# ADDA.net
KiCad netlist of a schematic drawn in EasyEDA Pro
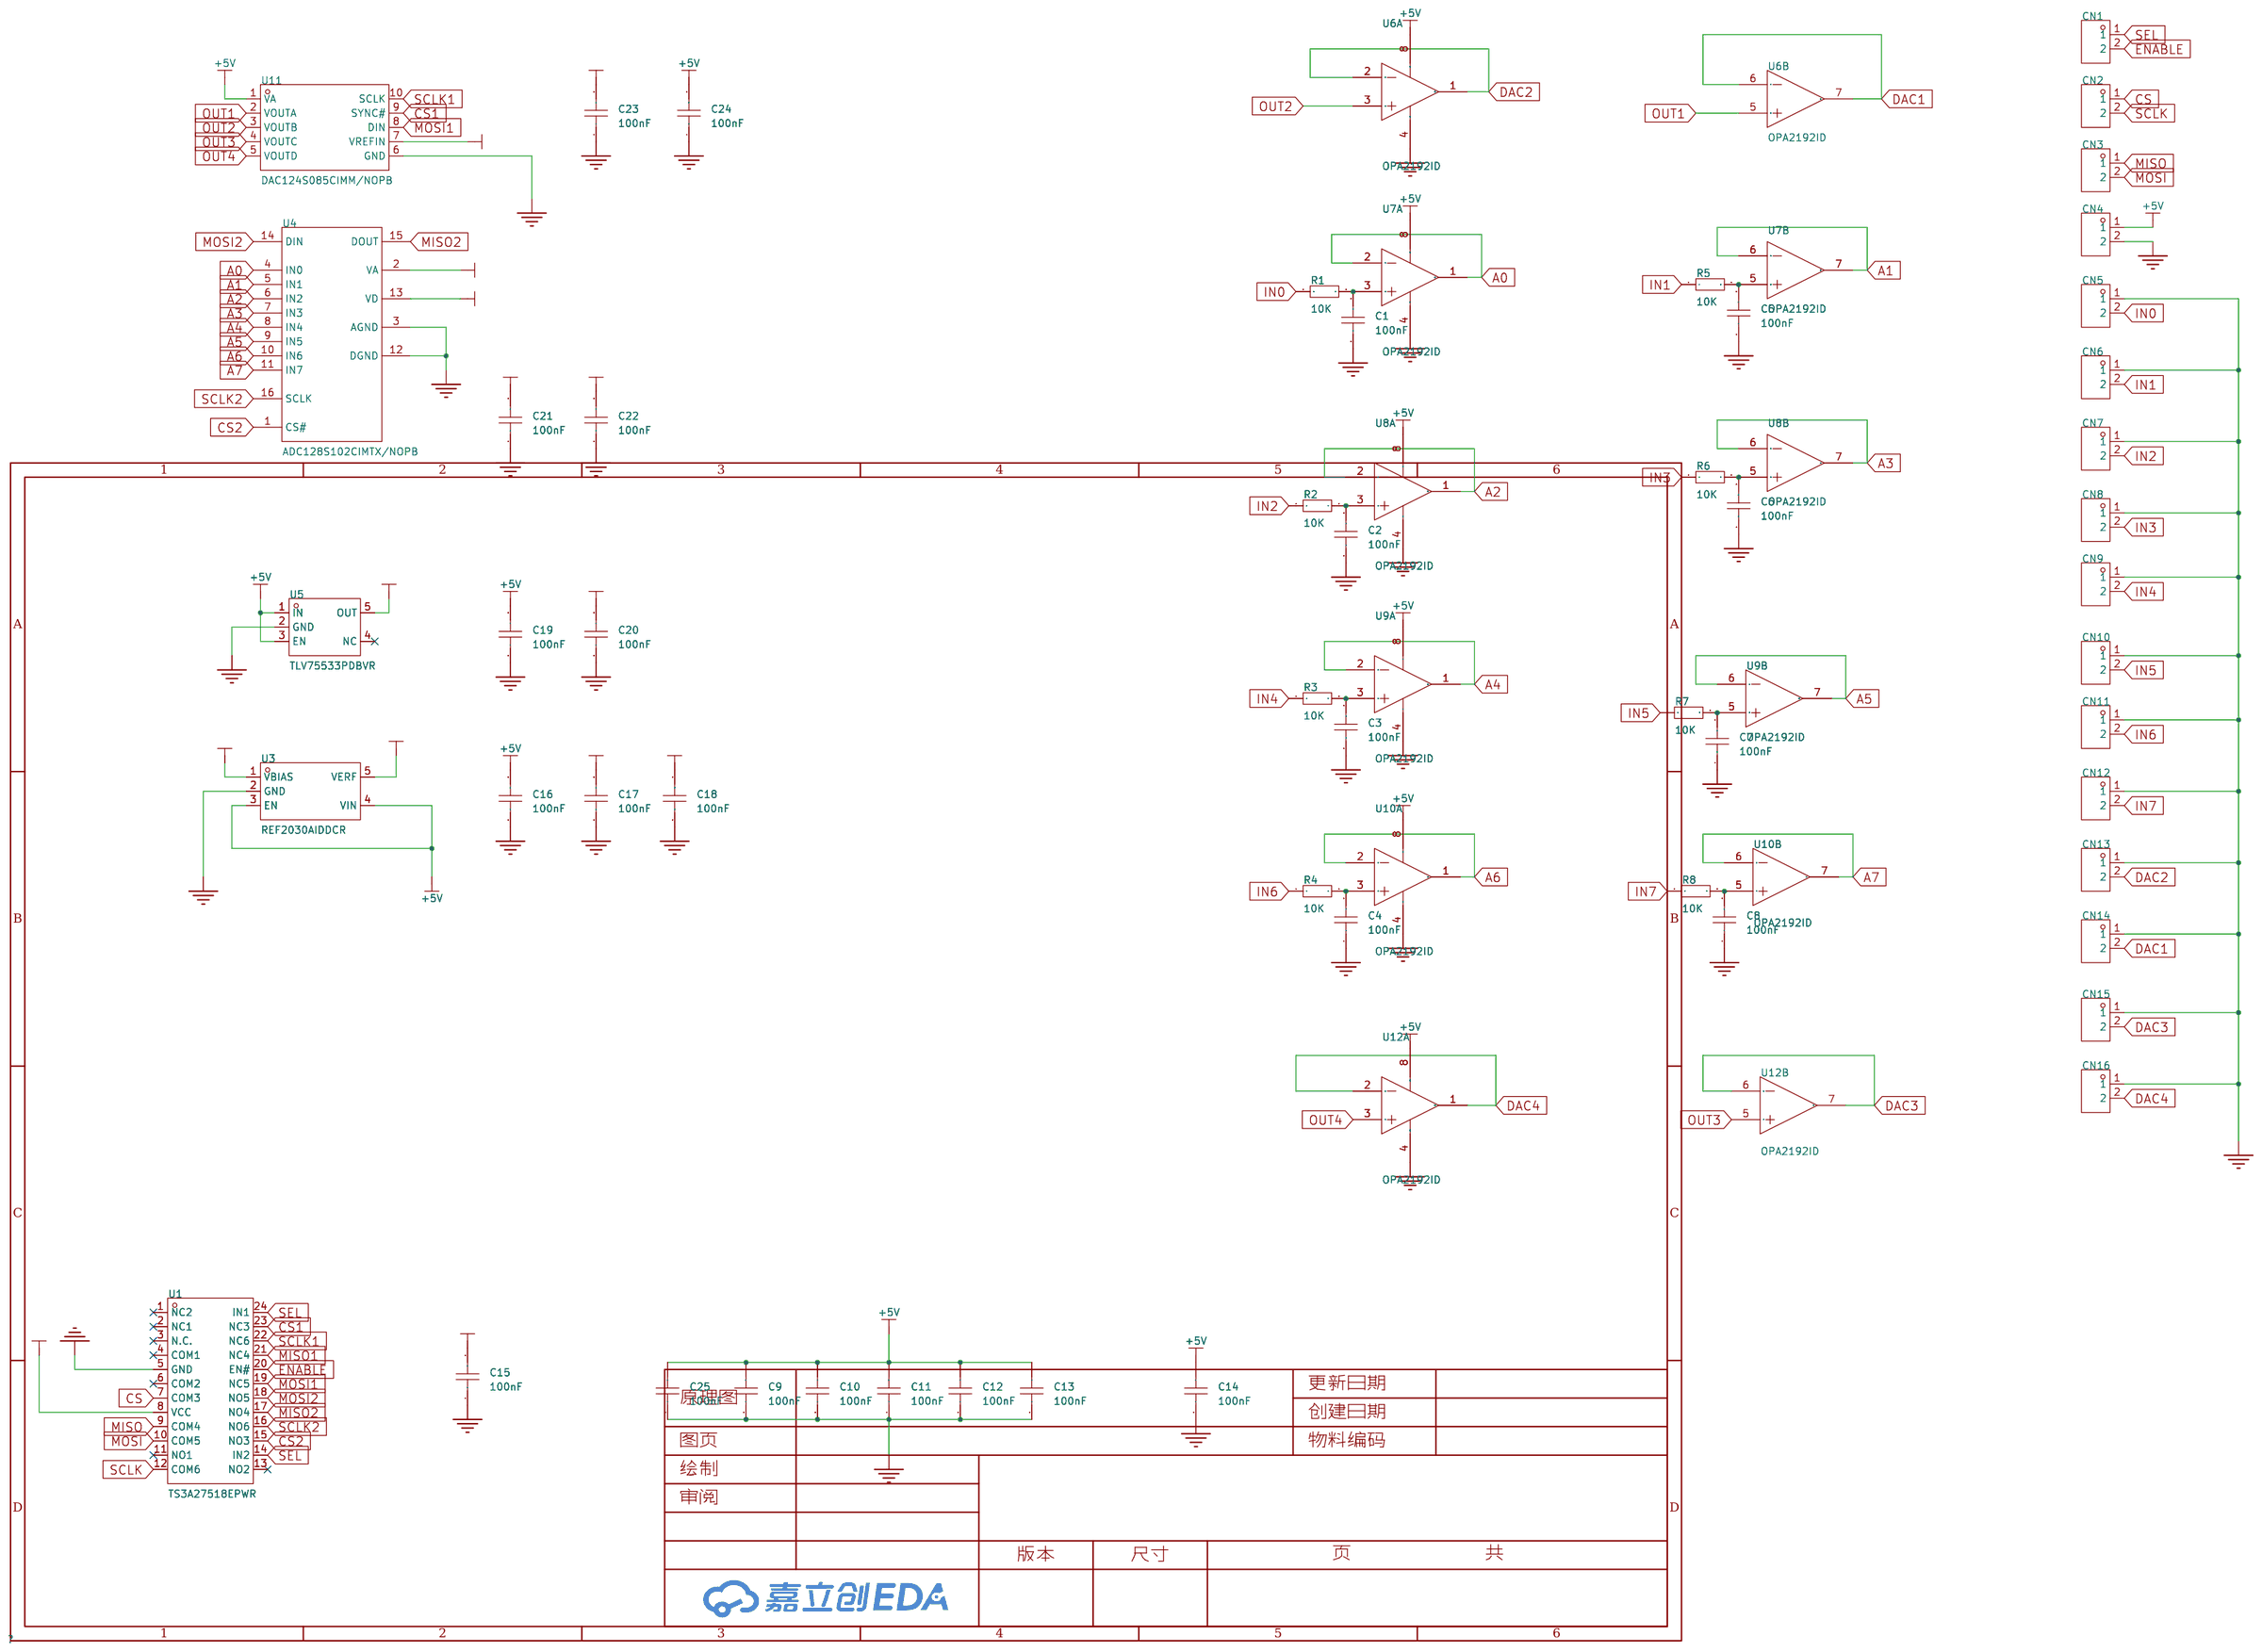
[diagram p0: schematic sheet]

(export (version "E")
  (design (tool "Eeschema 10.0.6"))
  (components
    (comp (ref "C1")
      (value "100nF")
      (footprint "easyedapro:C0805")
      (libsource (lib "easyedapro") (part "CapAcitance"))
    )
    (comp (ref "C2")
      (value "100nF")
      (footprint "easyedapro:C0805")
      (libsource (lib "easyedapro") (part "CapAcitance"))
    )
    (comp (ref "C3")
      (value "100nF")
      (footprint "easyedapro:C0805")
      (libsource (lib "easyedapro") (part "CapAcitance"))
    )
    (comp (ref "C4")
      (value "100nF")
      (footprint "easyedapro:C0805")
      (libsource (lib "easyedapro") (part "CapAcitance"))
    )
    (comp (ref "C5")
      (value "100nF")
      (footprint "easyedapro:C0805")
      (libsource (lib "easyedapro") (part "CapAcitance"))
    )
    (comp (ref "C6")
      (value "100nF")
      (footprint "easyedapro:C0805")
      (libsource (lib "easyedapro") (part "CapAcitance"))
    )
    (comp (ref "C7")
      (value "100nF")
      (footprint "easyedapro:C0805")
      (libsource (lib "easyedapro") (part "CapAcitance"))
    )
    (comp (ref "C8")
      (value "100nF")
      (footprint "easyedapro:C0805")
      (libsource (lib "easyedapro") (part "CapAcitance"))
    )
    (comp (ref "C9")
      (value "100nF")
      (footprint "easyedapro:C0805")
      (libsource (lib "easyedapro") (part "CapAcitance"))
    )
    (comp (ref "C10")
      (value "100nF")
      (footprint "easyedapro:C0805")
      (libsource (lib "easyedapro") (part "CapAcitance"))
    )
    (comp (ref "C11")
      (value "100nF")
      (footprint "easyedapro:C0805")
      (libsource (lib "easyedapro") (part "CapAcitance"))
    )
    (comp (ref "C12")
      (value "100nF")
      (footprint "easyedapro:C0805")
      (libsource (lib "easyedapro") (part "CapAcitance"))
    )
    (comp (ref "C13")
      (value "100nF")
      (footprint "easyedapro:C0805")
      (libsource (lib "easyedapro") (part "CapAcitance"))
    )
    (comp (ref "C14")
      (value "100nF")
      (footprint "easyedapro:C0805")
      (libsource (lib "easyedapro") (part "CapAcitance"))
    )
    (comp (ref "C15")
      (value "100nF")
      (footprint "easyedapro:C0805")
      (libsource (lib "easyedapro") (part "CapAcitance"))
    )
    (comp (ref "C16")
      (value "100nF")
      (footprint "easyedapro:C0805")
      (libsource (lib "easyedapro") (part "CapAcitance"))
    )
    (comp (ref "C17")
      (value "100nF")
      (footprint "easyedapro:C0805")
      (libsource (lib "easyedapro") (part "CapAcitance"))
    )
    (comp (ref "C18")
      (value "100nF")
      (footprint "easyedapro:C0805")
      (libsource (lib "easyedapro") (part "CapAcitance"))
    )
    (comp (ref "C19")
      (value "100nF")
      (footprint "easyedapro:C0805")
      (libsource (lib "easyedapro") (part "CapAcitance"))
    )
    (comp (ref "C20")
      (value "100nF")
      (footprint "easyedapro:C0805")
      (libsource (lib "easyedapro") (part "CapAcitance"))
    )
    (comp (ref "C21")
      (value "100nF")
      (footprint "easyedapro:C0805")
      (libsource (lib "easyedapro") (part "CapAcitance"))
    )
    (comp (ref "C22")
      (value "100nF")
      (footprint "easyedapro:C0805")
      (libsource (lib "easyedapro") (part "CapAcitance"))
    )
    (comp (ref "C23")
      (value "100nF")
      (footprint "easyedapro:C0805")
      (libsource (lib "easyedapro") (part "CapAcitance"))
    )
    (comp (ref "C24")
      (value "100nF")
      (footprint "easyedapro:C0805")
      (libsource (lib "easyedapro") (part "CapAcitance"))
    )
    (comp (ref "C25")
      (value "100nF")
      (footprint "easyedapro:C0805")
      (libsource (lib "easyedapro") (part "CapAcitance"))
    )
    (comp (ref "CN1")
      (value "CON2-2.54*2P")
      (footprint "easyedapro:CONN-TH_2P-P2.54-V")
      (libsource (lib "easyedapro") (part "CON2-2.54*2P"))
    )
    (comp (ref "CN2")
      (value "CON2-2.54*2P")
      (footprint "easyedapro:CONN-TH_2P-P2.54-V")
      (libsource (lib "easyedapro") (part "CON2-2.54*2P"))
    )
    (comp (ref "CN3")
      (value "CON2-2.54*2P")
      (footprint "easyedapro:CONN-TH_2P-P2.54-V")
      (libsource (lib "easyedapro") (part "CON2-2.54*2P"))
    )
    (comp (ref "CN4")
      (value "CON2-2.54*2P")
      (footprint "easyedapro:CONN-TH_2P-P2.54-V")
      (libsource (lib "easyedapro") (part "CON2-2.54*2P"))
    )
    (comp (ref "CN5")
      (value "CON2-2.54*2P")
      (footprint "easyedapro:CONN-TH_2P-P2.54-V")
      (libsource (lib "easyedapro") (part "CON2-2.54*2P"))
    )
    (comp (ref "CN6")
      (value "CON2-2.54*2P")
      (footprint "easyedapro:CONN-TH_2P-P2.54-V")
      (libsource (lib "easyedapro") (part "CON2-2.54*2P"))
    )
    (comp (ref "CN7")
      (value "CON2-2.54*2P")
      (footprint "easyedapro:CONN-TH_2P-P2.54-V")
      (libsource (lib "easyedapro") (part "CON2-2.54*2P"))
    )
    (comp (ref "CN8")
      (value "CON2-2.54*2P")
      (footprint "easyedapro:CONN-TH_2P-P2.54-V")
      (libsource (lib "easyedapro") (part "CON2-2.54*2P"))
    )
    (comp (ref "CN9")
      (value "CON2-2.54*2P")
      (footprint "easyedapro:CONN-TH_2P-P2.54-V")
      (libsource (lib "easyedapro") (part "CON2-2.54*2P"))
    )
    (comp (ref "CN10")
      (value "CON2-2.54*2P")
      (footprint "easyedapro:CONN-TH_2P-P2.54-V")
      (libsource (lib "easyedapro") (part "CON2-2.54*2P"))
    )
    (comp (ref "CN11")
      (value "CON2-2.54*2P")
      (footprint "easyedapro:CONN-TH_2P-P2.54-V")
      (libsource (lib "easyedapro") (part "CON2-2.54*2P"))
    )
    (comp (ref "CN12")
      (value "CON2-2.54*2P")
      (footprint "easyedapro:CONN-TH_2P-P2.54-V")
      (libsource (lib "easyedapro") (part "CON2-2.54*2P"))
    )
    (comp (ref "CN13")
      (value "CON2-2.54*2P")
      (footprint "easyedapro:CONN-TH_2P-P2.54-V")
      (libsource (lib "easyedapro") (part "CON2-2.54*2P"))
    )
    (comp (ref "CN14")
      (value "CON2-2.54*2P")
      (footprint "easyedapro:CONN-TH_2P-P2.54-V")
      (libsource (lib "easyedapro") (part "CON2-2.54*2P"))
    )
    (comp (ref "CN15")
      (value "CON2-2.54*2P")
      (footprint "easyedapro:CONN-TH_2P-P2.54-V")
      (libsource (lib "easyedapro") (part "CON2-2.54*2P"))
    )
    (comp (ref "CN16")
      (value "CON2-2.54*2P")
      (footprint "easyedapro:CONN-TH_2P-P2.54-V")
      (libsource (lib "easyedapro") (part "CON2-2.54*2P"))
    )
    (comp (ref "R1") (value "10K") (footprint "easyedapro:R0805") (libsource (lib "easyedapro") (part "电阻")))
    (comp (ref "R2") (value "10K") (footprint "easyedapro:R0805") (libsource (lib "easyedapro") (part "电阻")))
    (comp (ref "R3") (value "10K") (footprint "easyedapro:R0805") (libsource (lib "easyedapro") (part "电阻")))
    (comp (ref "R4") (value "10K") (footprint "easyedapro:R0805") (libsource (lib "easyedapro") (part "电阻")))
    (comp (ref "R5") (value "10K") (footprint "easyedapro:R0805") (libsource (lib "easyedapro") (part "电阻")))
    (comp (ref "R6") (value "10K") (footprint "easyedapro:R0805") (libsource (lib "easyedapro") (part "电阻")))
    (comp (ref "R7") (value "10K") (footprint "easyedapro:R0805") (libsource (lib "easyedapro") (part "电阻")))
    (comp (ref "R8") (value "10K") (footprint "easyedapro:R0805") (libsource (lib "easyedapro") (part "电阻")))
    (comp (ref "U1")
      (value "TS3A27518EPWR")
      (footprint "easyedapro:TSSOP-24_L7.8-W4.4-P0.65-LS6.4-BL")
      (description "开关电路:-;通道数:6;导通电阻:6.2Ω;")
      (fields (field (name "Manufacturer") "TI(德州仪器)"))
      (libsource (lib "easyedapro") (part "TS3A27518EPWR"))
    )
    (comp (ref "U3")
      (value "REF2030AIDDCR")
      (footprint "easyedapro:SOT-23-5_L2.9-W1.6-P0.95-LS2.8-BL")
      (description "输出类型:固定;输入电压:3.02V~5.5V;输出电压:1.5V；3V;输出电流:20mA;精度:±0.05%;")
      (fields (field (name "Manufacturer") "TI(德州仪器)"))
      (libsource (lib "easyedapro") (part "REF2030AIDDCR"))
    )
    (comp (ref "U4")
      (value "ADC128S102CIMTX/NOPB")
      (footprint "easyedapro:TSSOP-16_L5.0-W4.4-P0.65-LS6.4-BL")
      (description "接口:SPI；DSP;电源电压:2.7V~5.25V;采样率:1MHz;分辨率:12位;")
      (fields (field (name "Manufacturer") "TI(德州仪器)"))
      (libsource (lib "easyedapro") (part "ADC128S102CIMTX/NOPB"))
    )
    (comp (ref "U5")
      (value "TLV75533PDBVR")
      (footprint "easyedapro:SOT-23-5_L3.0-W1.7-P0.95-LS2.8-BR")
      (description "输出类型:固定;最大输入电压:5.5V;输出电压:3.3V;输出电流:500mA;电源纹波抑制比(PSRR):52dB;输出极性:正极;")
      (fields (field (name "Manufacturer") "TI(德州仪器)"))
      (libsource (lib "easyedapro") (part "TLV75533PDBVR"))
    )
    (comp (ref "U6")
      (value "OPA2192ID")
      (footprint "easyedapro:SOIC-8_L4.9-W3.9-P1.27-LS6.0-BL")
      (description "放大器数:双路;增益带宽积(GBP):10MHz;输入偏置电流(Ib):5pA;输入失调电压(Vos):5uV;压摆率(SR):20V/us;带宽(-3db):-;轨到轨:-;")
      (fields (field (name "Manufacturer") "TI(德州仪器)"))
      (libsource (lib "easyedapro") (part "OPA2192ID"))
    )
    (comp (ref "U7")
      (value "OPA2192ID")
      (footprint "easyedapro:SOIC-8_L4.9-W3.9-P1.27-LS6.0-BL")
      (description "放大器数:双路;增益带宽积(GBP):10MHz;输入偏置电流(Ib):5pA;输入失调电压(Vos):5uV;压摆率(SR):20V/us;带宽(-3db):-;轨到轨:-;")
      (fields (field (name "Manufacturer") "TI(德州仪器)"))
      (libsource (lib "easyedapro") (part "OPA2192ID"))
    )
    (comp (ref "U8")
      (value "OPA2192ID")
      (footprint "easyedapro:SOIC-8_L4.9-W3.9-P1.27-LS6.0-BL")
      (description "放大器数:双路;增益带宽积(GBP):10MHz;输入偏置电流(Ib):5pA;输入失调电压(Vos):5uV;压摆率(SR):20V/us;带宽(-3db):-;轨到轨:-;")
      (fields (field (name "Manufacturer") "TI(德州仪器)"))
      (libsource (lib "easyedapro") (part "OPA2192ID"))
    )
    (comp (ref "U9")
      (value "OPA2192ID")
      (footprint "easyedapro:SOIC-8_L4.9-W3.9-P1.27-LS6.0-BL")
      (description "放大器数:双路;增益带宽积(GBP):10MHz;输入偏置电流(Ib):5pA;输入失调电压(Vos):5uV;压摆率(SR):20V/us;带宽(-3db):-;轨到轨:-;")
      (fields (field (name "Manufacturer") "TI(德州仪器)"))
      (libsource (lib "easyedapro") (part "OPA2192ID"))
    )
    (comp (ref "U10")
      (value "OPA2192ID")
      (footprint "easyedapro:SOIC-8_L4.9-W3.9-P1.27-LS6.0-BL")
      (description "放大器数:双路;增益带宽积(GBP):10MHz;输入偏置电流(Ib):5pA;输入失调电压(Vos):5uV;压摆率(SR):20V/us;带宽(-3db):-;轨到轨:-;")
      (fields (field (name "Manufacturer") "TI(德州仪器)"))
      (libsource (lib "easyedapro") (part "OPA2192ID"))
    )
    (comp (ref "U11")
      (value "DAC124S085CIMM/NOPB")
      (footprint "easyedapro:VSSOP-10_L3.0-W3.0-P0.50-LS4.9-BL")
      (description "分辨率:12位;接口类型:SPI；QSPI；MICROWIRE;工作电压:2.7V~5.5V;稳定时间:8.5us;INL/DNL:8LSB;")
      (fields (field (name "Manufacturer") "TI(德州仪器)"))
      (libsource (lib "easyedapro") (part "DAC124S085CIMM/NOPB"))
    )
    (comp (ref "U12")
      (value "OPA2192ID")
      (footprint "easyedapro:SOIC-8_L4.9-W3.9-P1.27-LS6.0-BL")
      (description "放大器数:双路;增益带宽积(GBP):10MHz;输入偏置电流(Ib):5pA;输入失调电压(Vos):5uV;压摆率(SR):20V/us;带宽(-3db):-;轨到轨:-;")
      (fields (field (name "Manufacturer") "TI(德州仪器)"))
      (libsource (lib "easyedapro") (part "OPA2192ID"))
    )
  )
  (nets
    (net (code "1") (name "+5V") (class "Default")
      (node (ref "C10") (pin "2") (pinfunction "2_2") (pintype "input"))
      (node (ref "C11") (pin "2") (pinfunction "2_2") (pintype "input"))
      (node (ref "C12") (pin "2") (pinfunction "2_2") (pintype "input"))
      (node (ref "C13") (pin "2") (pinfunction "2_2") (pintype "input"))
      (node (ref "C14") (pin "2") (pinfunction "2_2") (pintype "input"))
      (node (ref "C16") (pin "2") (pinfunction "2_2") (pintype "input"))
      (node (ref "C19") (pin "2") (pinfunction "2_2") (pintype "input"))
      (node (ref "C24") (pin "2") (pinfunction "2_2") (pintype "input"))
      (node (ref "C25") (pin "2") (pinfunction "2_2") (pintype "input"))
      (node (ref "C9") (pin "2") (pinfunction "2_2") (pintype "input"))
      (node (ref "CN4") (pin "1") (pinfunction "1_1") (pintype "unspecified"))
      (node (ref "U10") (pin "8") (pinfunction "VCC_8") (pintype "unspecified"))
      (node (ref "U11") (pin "1") (pinfunction "VA_1") (pintype "unspecified"))
      (node (ref "U12") (pin "8") (pinfunction "VCC_8") (pintype "unspecified"))
      (node (ref "U3") (pin "3") (pinfunction "EN_3") (pintype "unspecified"))
      (node (ref "U3") (pin "4") (pinfunction "VIN_4") (pintype "unspecified"))
      (node (ref "U5") (pin "1") (pinfunction "IN_1") (pintype "unspecified"))
      (node (ref "U5") (pin "3") (pinfunction "EN_3") (pintype "unspecified"))
      (node (ref "U6") (pin "8") (pinfunction "VCC_8") (pintype "unspecified"))
      (node (ref "U7") (pin "8") (pinfunction "VCC_8") (pintype "unspecified"))
      (node (ref "U8") (pin "8") (pinfunction "VCC_8") (pintype "unspecified"))
      (node (ref "U9") (pin "8") (pinfunction "VCC_8") (pintype "unspecified"))
    )
    (net (code "2") (name "1.5V") (class "Default")
      (node (ref "C17") (pin "2") (pinfunction "2_2") (pintype "input"))
      (node (ref "U3") (pin "1") (pinfunction "VBIAS_1") (pintype "unspecified"))
    )
    (net (code "3") (name "3.3V") (class "Default")
      (node (ref "C15") (pin "2") (pinfunction "2_2") (pintype "input"))
      (node (ref "C20") (pin "2") (pinfunction "2_2") (pintype "input"))
      (node (ref "C21") (pin "2") (pinfunction "2_2") (pintype "input"))
      (node (ref "U1") (pin "8") (pinfunction "VCC_8") (pintype "unspecified"))
      (node (ref "U4") (pin "13") (pinfunction "VD_13") (pintype "unspecified"))
      (node (ref "U5") (pin "5") (pinfunction "OUT_5") (pintype "unspecified"))
    )
    (net (code "4") (name "3V") (class "Default")
      (node (ref "C18") (pin "2") (pinfunction "2_2") (pintype "input"))
      (node (ref "C22") (pin "2") (pinfunction "2_2") (pintype "input"))
      (node (ref "C23") (pin "2") (pinfunction "2_2") (pintype "input"))
      (node (ref "U11") (pin "7") (pinfunction "VREFIN_7") (pintype "unspecified"))
      (node (ref "U3") (pin "5") (pinfunction "VERF_5") (pintype "unspecified"))
      (node (ref "U4") (pin "2") (pinfunction "VA_2") (pintype "unspecified"))
    )
    (net (code "5") (name "A0") (class "Default")
      (node (ref "U4") (pin "4") (pinfunction "IN0_4") (pintype "unspecified"))
      (node (ref "U7") (pin "1") (pinfunction "OUT1_1") (pintype "output"))
      (node (ref "U7") (pin "2") (pinfunction "IN1-_2") (pintype "unspecified"))
    )
    (net (code "6") (name "A1") (class "Default")
      (node (ref "U4") (pin "5") (pinfunction "IN1_5") (pintype "unspecified"))
      (node (ref "U7") (pin "6") (pinfunction "IN2-_6") (pintype "unspecified"))
      (node (ref "U7") (pin "7") (pinfunction "OUT2_7") (pintype "output"))
    )
    (net (code "7") (name "A2") (class "Default")
      (node (ref "U4") (pin "6") (pinfunction "IN2_6") (pintype "unspecified"))
      (node (ref "U8") (pin "1") (pinfunction "OUT1_1") (pintype "output"))
      (node (ref "U8") (pin "2") (pinfunction "IN1-_2") (pintype "unspecified"))
    )
    (net (code "8") (name "A3") (class "Default")
      (node (ref "U4") (pin "7") (pinfunction "IN3_7") (pintype "unspecified"))
      (node (ref "U8") (pin "6") (pinfunction "IN2-_6") (pintype "unspecified"))
      (node (ref "U8") (pin "7") (pinfunction "OUT2_7") (pintype "output"))
    )
    (net (code "9") (name "A4") (class "Default")
      (node (ref "U4") (pin "8") (pinfunction "IN4_8") (pintype "unspecified"))
      (node (ref "U9") (pin "1") (pinfunction "OUT1_1") (pintype "output"))
      (node (ref "U9") (pin "2") (pinfunction "IN1-_2") (pintype "unspecified"))
    )
    (net (code "10") (name "A5") (class "Default")
      (node (ref "U4") (pin "9") (pinfunction "IN5_9") (pintype "unspecified"))
      (node (ref "U9") (pin "6") (pinfunction "IN2-_6") (pintype "unspecified"))
      (node (ref "U9") (pin "7") (pinfunction "OUT2_7") (pintype "output"))
    )
    (net (code "11") (name "A6") (class "Default")
      (node (ref "U10") (pin "1") (pinfunction "OUT1_1") (pintype "output"))
      (node (ref "U10") (pin "2") (pinfunction "IN1-_2") (pintype "unspecified"))
      (node (ref "U4") (pin "10") (pinfunction "IN6_10") (pintype "unspecified"))
    )
    (net (code "12") (name "A7") (class "Default")
      (node (ref "U10") (pin "6") (pinfunction "IN2-_6") (pintype "unspecified"))
      (node (ref "U10") (pin "7") (pinfunction "OUT2_7") (pintype "output"))
      (node (ref "U4") (pin "11") (pinfunction "IN7_11") (pintype "unspecified"))
    )
    (net (code "13") (name "CS") (class "Default")
      (node (ref "CN2") (pin "1") (pinfunction "1_1") (pintype "unspecified"))
      (node (ref "U1") (pin "7") (pinfunction "COM3_7") (pintype "unspecified"))
    )
    (net (code "14") (name "CS1") (class "Default")
      (node (ref "U1") (pin "23") (pinfunction "NC3_23") (pintype "unspecified"))
      (node (ref "U11") (pin "9") (pinfunction "SYNC#_9") (pintype "unspecified"))
    )
    (net (code "15") (name "CS2") (class "Default")
      (node (ref "U1") (pin "15") (pinfunction "NO3_15") (pintype "unspecified"))
      (node (ref "U4") (pin "1") (pinfunction "CS#_1") (pintype "unspecified"))
    )
    (net (code "16") (name "DAC1") (class "Default")
      (node (ref "CN14") (pin "2") (pinfunction "2_2") (pintype "unspecified"))
      (node (ref "U6") (pin "6") (pinfunction "IN2-_6") (pintype "unspecified"))
      (node (ref "U6") (pin "7") (pinfunction "OUT2_7") (pintype "output"))
    )
    (net (code "17") (name "DAC2") (class "Default")
      (node (ref "CN13") (pin "2") (pinfunction "2_2") (pintype "unspecified"))
      (node (ref "U6") (pin "1") (pinfunction "OUT1_1") (pintype "output"))
      (node (ref "U6") (pin "2") (pinfunction "IN1-_2") (pintype "unspecified"))
    )
    (net (code "18") (name "DAC3") (class "Default")
      (node (ref "CN15") (pin "2") (pinfunction "2_2") (pintype "unspecified"))
      (node (ref "U12") (pin "6") (pinfunction "IN2-_6") (pintype "unspecified"))
      (node (ref "U12") (pin "7") (pinfunction "OUT2_7") (pintype "output"))
    )
    (net (code "19") (name "DAC4") (class "Default")
      (node (ref "CN16") (pin "2") (pinfunction "2_2") (pintype "unspecified"))
      (node (ref "U12") (pin "1") (pinfunction "OUT1_1") (pintype "output"))
      (node (ref "U12") (pin "2") (pinfunction "IN1-_2") (pintype "unspecified"))
    )
    (net (code "20") (name "ENABLE") (class "Default")
      (node (ref "CN1") (pin "2") (pinfunction "2_2") (pintype "unspecified"))
      (node (ref "U1") (pin "20") (pinfunction "EN#_20") (pintype "unspecified"))
    )
    (net (code "21") (name "GND") (class "Default")
      (node (ref "C1") (pin "1") (pinfunction "1_1") (pintype "input"))
      (node (ref "C10") (pin "1") (pinfunction "1_1") (pintype "input"))
      (node (ref "C11") (pin "1") (pinfunction "1_1") (pintype "input"))
      (node (ref "C12") (pin "1") (pinfunction "1_1") (pintype "input"))
      (node (ref "C13") (pin "1") (pinfunction "1_1") (pintype "input"))
      (node (ref "C14") (pin "1") (pinfunction "1_1") (pintype "input"))
      (node (ref "C15") (pin "1") (pinfunction "1_1") (pintype "input"))
      (node (ref "C16") (pin "1") (pinfunction "1_1") (pintype "input"))
      (node (ref "C17") (pin "1") (pinfunction "1_1") (pintype "input"))
      (node (ref "C18") (pin "1") (pinfunction "1_1") (pintype "input"))
      (node (ref "C19") (pin "1") (pinfunction "1_1") (pintype "input"))
      (node (ref "C2") (pin "1") (pinfunction "1_1") (pintype "input"))
      (node (ref "C20") (pin "1") (pinfunction "1_1") (pintype "input"))
      (node (ref "C21") (pin "1") (pinfunction "1_1") (pintype "input"))
      (node (ref "C22") (pin "1") (pinfunction "1_1") (pintype "input"))
      (node (ref "C23") (pin "1") (pinfunction "1_1") (pintype "input"))
      (node (ref "C24") (pin "1") (pinfunction "1_1") (pintype "input"))
      (node (ref "C25") (pin "1") (pinfunction "1_1") (pintype "input"))
      (node (ref "C3") (pin "1") (pinfunction "1_1") (pintype "input"))
      (node (ref "C4") (pin "1") (pinfunction "1_1") (pintype "input"))
      (node (ref "C5") (pin "1") (pinfunction "1_1") (pintype "input"))
      (node (ref "C6") (pin "1") (pinfunction "1_1") (pintype "input"))
      (node (ref "C7") (pin "1") (pinfunction "1_1") (pintype "input"))
      (node (ref "C8") (pin "1") (pinfunction "1_1") (pintype "input"))
      (node (ref "C9") (pin "1") (pinfunction "1_1") (pintype "input"))
      (node (ref "CN10") (pin "1") (pinfunction "1_1") (pintype "unspecified"))
      (node (ref "CN11") (pin "1") (pinfunction "1_1") (pintype "unspecified"))
      (node (ref "CN12") (pin "1") (pinfunction "1_1") (pintype "unspecified"))
      (node (ref "CN13") (pin "1") (pinfunction "1_1") (pintype "unspecified"))
      (node (ref "CN14") (pin "1") (pinfunction "1_1") (pintype "unspecified"))
      (node (ref "CN15") (pin "1") (pinfunction "1_1") (pintype "unspecified"))
      (node (ref "CN16") (pin "1") (pinfunction "1_1") (pintype "unspecified"))
      (node (ref "CN4") (pin "2") (pinfunction "2_2") (pintype "unspecified"))
      (node (ref "CN5") (pin "1") (pinfunction "1_1") (pintype "unspecified"))
      (node (ref "CN6") (pin "1") (pinfunction "1_1") (pintype "unspecified"))
      (node (ref "CN7") (pin "1") (pinfunction "1_1") (pintype "unspecified"))
      (node (ref "CN8") (pin "1") (pinfunction "1_1") (pintype "unspecified"))
      (node (ref "CN9") (pin "1") (pinfunction "1_1") (pintype "unspecified"))
      (node (ref "U1") (pin "5") (pinfunction "GND_5") (pintype "unspecified"))
      (node (ref "U10") (pin "4") (pinfunction "GND_4") (pintype "unspecified"))
      (node (ref "U11") (pin "6") (pinfunction "GND_6") (pintype "unspecified"))
      (node (ref "U12") (pin "4") (pinfunction "GND_4") (pintype "unspecified"))
      (node (ref "U3") (pin "2") (pinfunction "GND_2") (pintype "unspecified"))
      (node (ref "U4") (pin "12") (pinfunction "DGND_12") (pintype "unspecified"))
      (node (ref "U4") (pin "3") (pinfunction "AGND_3") (pintype "unspecified"))
      (node (ref "U5") (pin "2") (pinfunction "GND_2") (pintype "unspecified"))
      (node (ref "U6") (pin "4") (pinfunction "GND_4") (pintype "unspecified"))
      (node (ref "U7") (pin "4") (pinfunction "GND_4") (pintype "unspecified"))
      (node (ref "U8") (pin "4") (pinfunction "GND_4") (pintype "unspecified"))
      (node (ref "U9") (pin "4") (pinfunction "GND_4") (pintype "unspecified"))
    )
    (net (code "22") (name "IN0") (class "Default")
      (node (ref "CN5") (pin "2") (pinfunction "2_2") (pintype "unspecified"))
      (node (ref "R1") (pin "1") (pinfunction "1_1") (pintype "input"))
    )
    (net (code "23") (name "IN1") (class "Default")
      (node (ref "CN6") (pin "2") (pinfunction "2_2") (pintype "unspecified"))
      (node (ref "R5") (pin "1") (pinfunction "1_1") (pintype "input"))
    )
    (net (code "24") (name "IN2") (class "Default")
      (node (ref "CN7") (pin "2") (pinfunction "2_2") (pintype "unspecified"))
      (node (ref "R2") (pin "1") (pinfunction "1_1") (pintype "input"))
    )
    (net (code "25") (name "IN3") (class "Default")
      (node (ref "CN8") (pin "2") (pinfunction "2_2") (pintype "unspecified"))
      (node (ref "R6") (pin "1") (pinfunction "1_1") (pintype "input"))
    )
    (net (code "26") (name "IN4") (class "Default")
      (node (ref "CN9") (pin "2") (pinfunction "2_2") (pintype "unspecified"))
      (node (ref "R3") (pin "1") (pinfunction "1_1") (pintype "input"))
    )
    (net (code "27") (name "IN5") (class "Default")
      (node (ref "CN10") (pin "2") (pinfunction "2_2") (pintype "unspecified"))
      (node (ref "R7") (pin "1") (pinfunction "1_1") (pintype "input"))
    )
    (net (code "28") (name "IN6") (class "Default")
      (node (ref "CN11") (pin "2") (pinfunction "2_2") (pintype "unspecified"))
      (node (ref "R4") (pin "1") (pinfunction "1_1") (pintype "input"))
    )
    (net (code "29") (name "IN7") (class "Default")
      (node (ref "CN12") (pin "2") (pinfunction "2_2") (pintype "unspecified"))
      (node (ref "R8") (pin "1") (pinfunction "1_1") (pintype "input"))
    )
    (net (code "30") (name "MISO") (class "Default")
      (node (ref "CN3") (pin "1") (pinfunction "1_1") (pintype "unspecified"))
      (node (ref "U1") (pin "9") (pinfunction "COM4_9") (pintype "unspecified"))
    )
    (net (code "31") (name "MISO1") (class "Default")
      (node (ref "U1") (pin "21") (pinfunction "NC4_21") (pintype "unspecified"))
    )
    (net (code "32") (name "MISO2") (class "Default")
      (node (ref "U1") (pin "17") (pinfunction "NO4_17") (pintype "unspecified"))
      (node (ref "U4") (pin "15") (pinfunction "DOUT_15") (pintype "output"))
    )
    (net (code "33") (name "MOSI") (class "Default")
      (node (ref "CN3") (pin "2") (pinfunction "2_2") (pintype "unspecified"))
      (node (ref "U1") (pin "10") (pinfunction "COM5_10") (pintype "unspecified"))
    )
    (net (code "34") (name "MOSI1") (class "Default")
      (node (ref "U1") (pin "19") (pinfunction "NC5_19") (pintype "unspecified"))
      (node (ref "U11") (pin "8") (pinfunction "DIN_8") (pintype "unspecified"))
    )
    (net (code "35") (name "MOSI2") (class "Default")
      (node (ref "U1") (pin "18") (pinfunction "NO5_18") (pintype "unspecified"))
      (node (ref "U4") (pin "14") (pinfunction "DIN_14") (pintype "unspecified"))
    )
    (net (code "36") (name "Net-(U7A-IN1+)") (class "Default")
      (node (ref "C1") (pin "2") (pinfunction "2_2") (pintype "input"))
      (node (ref "R1") (pin "2") (pinfunction "2_2") (pintype "input"))
      (node (ref "U7") (pin "3") (pinfunction "IN1+_3") (pintype "unspecified"))
    )
    (net (code "37") (name "Net-(U7B-IN2+)") (class "Default")
      (node (ref "C5") (pin "2") (pinfunction "2_2") (pintype "input"))
      (node (ref "R5") (pin "2") (pinfunction "2_2") (pintype "input"))
      (node (ref "U7") (pin "5") (pinfunction "IN2+_5") (pintype "unspecified"))
    )
    (net (code "38") (name "Net-(U8A-IN1+)") (class "Default")
      (node (ref "C2") (pin "2") (pinfunction "2_2") (pintype "input"))
      (node (ref "R2") (pin "2") (pinfunction "2_2") (pintype "input"))
      (node (ref "U8") (pin "3") (pinfunction "IN1+_3") (pintype "unspecified"))
    )
    (net (code "39") (name "Net-(U8B-IN2+)") (class "Default")
      (node (ref "C6") (pin "2") (pinfunction "2_2") (pintype "input"))
      (node (ref "R6") (pin "2") (pinfunction "2_2") (pintype "input"))
      (node (ref "U8") (pin "5") (pinfunction "IN2+_5") (pintype "unspecified"))
    )
    (net (code "40") (name "Net-(U9A-IN1+)") (class "Default")
      (node (ref "C3") (pin "2") (pinfunction "2_2") (pintype "input"))
      (node (ref "R3") (pin "2") (pinfunction "2_2") (pintype "input"))
      (node (ref "U9") (pin "3") (pinfunction "IN1+_3") (pintype "unspecified"))
    )
    (net (code "41") (name "Net-(U9B-IN2+)") (class "Default")
      (node (ref "C7") (pin "2") (pinfunction "2_2") (pintype "input"))
      (node (ref "R7") (pin "2") (pinfunction "2_2") (pintype "input"))
      (node (ref "U9") (pin "5") (pinfunction "IN2+_5") (pintype "unspecified"))
    )
    (net (code "42") (name "Net-(U10A-IN1+)") (class "Default")
      (node (ref "C4") (pin "2") (pinfunction "2_2") (pintype "input"))
      (node (ref "R4") (pin "2") (pinfunction "2_2") (pintype "input"))
      (node (ref "U10") (pin "3") (pinfunction "IN1+_3") (pintype "unspecified"))
    )
    (net (code "43") (name "Net-(U10B-IN2+)") (class "Default")
      (node (ref "C8") (pin "2") (pinfunction "2_2") (pintype "input"))
      (node (ref "R8") (pin "2") (pinfunction "2_2") (pintype "input"))
      (node (ref "U10") (pin "5") (pinfunction "IN2+_5") (pintype "unspecified"))
    )
    (net (code "44") (name "OUT1") (class "Default")
      (node (ref "U11") (pin "2") (pinfunction "VOUTA_2") (pintype "unspecified"))
      (node (ref "U6") (pin "5") (pinfunction "IN2+_5") (pintype "unspecified"))
    )
    (net (code "45") (name "OUT2") (class "Default")
      (node (ref "U11") (pin "3") (pinfunction "VOUTB_3") (pintype "unspecified"))
      (node (ref "U6") (pin "3") (pinfunction "IN1+_3") (pintype "unspecified"))
    )
    (net (code "46") (name "OUT3") (class "Default")
      (node (ref "U11") (pin "4") (pinfunction "VOUTC_4") (pintype "unspecified"))
      (node (ref "U12") (pin "5") (pinfunction "IN2+_5") (pintype "unspecified"))
    )
    (net (code "47") (name "OUT4") (class "Default")
      (node (ref "U11") (pin "5") (pinfunction "VOUTD_5") (pintype "unspecified"))
      (node (ref "U12") (pin "3") (pinfunction "IN1+_3") (pintype "unspecified"))
    )
    (net (code "48") (name "SCLK") (class "Default")
      (node (ref "CN2") (pin "2") (pinfunction "2_2") (pintype "unspecified"))
      (node (ref "U1") (pin "12") (pinfunction "COM6_12") (pintype "unspecified"))
    )
    (net (code "49") (name "SCLK1") (class "Default")
      (node (ref "U1") (pin "22") (pinfunction "NC6_22") (pintype "unspecified"))
      (node (ref "U11") (pin "10") (pinfunction "SCLK_10") (pintype "unspecified"))
    )
    (net (code "50") (name "SCLK2") (class "Default")
      (node (ref "U1") (pin "16") (pinfunction "NO6_16") (pintype "unspecified"))
      (node (ref "U4") (pin "16") (pinfunction "SCLK_16") (pintype "unspecified"))
    )
    (net (code "51") (name "SEL") (class "Default")
      (node (ref "CN1") (pin "1") (pinfunction "1_1") (pintype "unspecified"))
      (node (ref "U1") (pin "14") (pinfunction "IN2_14") (pintype "unspecified"))
      (node (ref "U1") (pin "24") (pinfunction "IN1_24") (pintype "unspecified"))
    )
    (net (code "52") (name "unconnected-(U1-COM1-Pad4)") (class "Default")
      (node (ref "U1") (pin "4") (pinfunction "COM1_4") (pintype "unspecified+no_connect"))
    )
    (net (code "53") (name "unconnected-(U1-COM2-Pad6)") (class "Default")
      (node (ref "U1") (pin "6") (pinfunction "COM2_6") (pintype "unspecified+no_connect"))
    )
    (net (code "54") (name "unconnected-(U1-N.C.-Pad3)") (class "Default")
      (node (ref "U1") (pin "3") (pinfunction "N.C._3") (pintype "unspecified+no_connect"))
    )
    (net (code "55") (name "unconnected-(U1-NC1-Pad2)") (class "Default")
      (node (ref "U1") (pin "2") (pinfunction "NC1_2") (pintype "unspecified+no_connect"))
    )
    (net (code "56") (name "unconnected-(U1-NC2-Pad1)") (class "Default")
      (node (ref "U1") (pin "1") (pinfunction "NC2_1") (pintype "unspecified+no_connect"))
    )
    (net (code "57") (name "unconnected-(U1-NO1-Pad11)") (class "Default")
      (node (ref "U1") (pin "11") (pinfunction "NO1_11") (pintype "unspecified+no_connect"))
    )
    (net (code "58") (name "unconnected-(U1-NO2-Pad13)") (class "Default")
      (node (ref "U1") (pin "13") (pinfunction "NO2_13") (pintype "unspecified+no_connect"))
    )
    (net (code "59") (name "unconnected-(U5-NC-Pad4)") (class "Default")
      (node (ref "U5") (pin "4") (pinfunction "NC_4") (pintype "unspecified+no_connect"))
    )
  )
)
